# MCU.net
KiCad netlist of a schematic drawn in Altium Designer
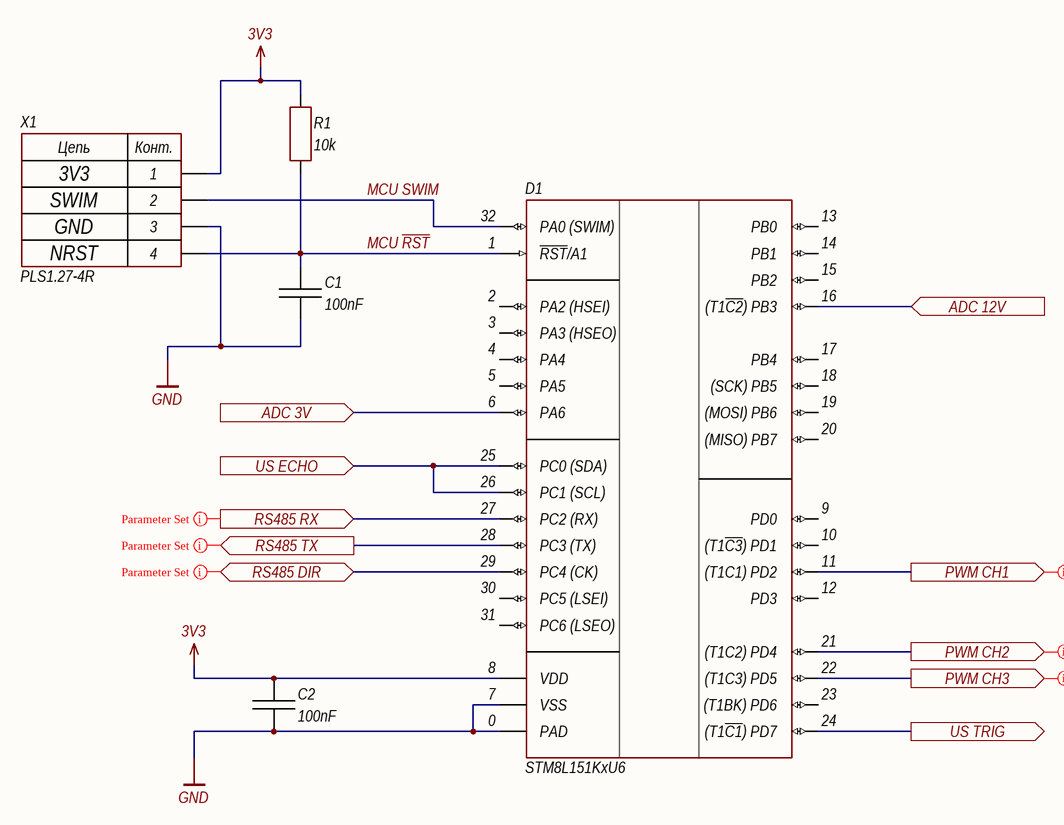
[diagram p0: MCU.SchDoc]

(export (version "E")
  (design (tool "Eeschema 10.0.6"))
  (components
    (comp (ref "C1")
      (value "100nF")
      (footprint "CH0402C")
      (fields (field (name "MANUFACTURER") "CCTC"))
      (libsource (lib "Discrete") (part "Capacitor"))
    )
    (comp (ref "C2")
      (value "100nF")
      (footprint "CH0402C")
      (fields (field (name "MANUFACTURER") "CCTC"))
      (libsource (lib "Discrete") (part "Capacitor"))
    )
    (comp (ref "D1")
      (value "STM8L151KxU6")
      (footprint "32-UFQFPN")
      (description "STM8")
      (fields (field (name "MANUFACTURER") "ST Microelectronics"))
      (libsource (lib "Digital") (part "STM8L151KxU6"))
    )
    (comp (ref "R1")
      (value "10k")
      (footprint "CH0402R")
      (fields (field (name "MANUFACTURER") "Uniroyal Elec"))
      (libsource (lib "Discrete") (part "Resistor"))
    )
    (comp (ref "X1")
      (value "PLS1.27-4R")
      (footprint "CON: PLS1.27-4R")
      (libsource (lib "Connectors") (part "4-Connector"))
    )
  )
  (nets
    (net (code "1") (name "/ADC 3V") (class "Default")
      (node (ref "D1") (pin "6") (pinfunction "PA6_6") (pintype "bidirectional"))
    )
    (net (code "2") (name "/ADC 12V") (class "Default")
      (node (ref "D1") (pin "16") (pinfunction "(T1~{C2})_PB3_16") (pintype "bidirectional"))
    )
    (net (code "3") (name "/MCU SWIM") (class "Default")
      (node (ref "D1") (pin "32") (pinfunction "PA0_(SWIM)_32") (pintype "bidirectional"))
      (node (ref "X1") (pin "2") (pinfunction "2_2") (pintype "passive"))
    )
    (net (code "4") (name "/MCU ~{RST}") (class "Default")
      (node (ref "C1") (pin "2") (pinfunction "2_2") (pintype "power_in"))
      (node (ref "D1") (pin "1") (pinfunction "~{RST}/A1_1") (pintype "input"))
      (node (ref "R1") (pin "1") (pinfunction "1_1") (pintype "passive"))
      (node (ref "X1") (pin "4") (pinfunction "4_4") (pintype "passive"))
    )
    (net (code "5") (name "/PWM CH1") (class "Default")
      (node (ref "D1") (pin "11") (pinfunction "(T1C1)_PD2_11") (pintype "bidirectional"))
    )
    (net (code "6") (name "/PWM CH2") (class "Default")
      (node (ref "D1") (pin "21") (pinfunction "(T1C2)_PD4_21") (pintype "bidirectional"))
    )
    (net (code "7") (name "/PWM CH3") (class "Default")
      (node (ref "D1") (pin "22") (pinfunction "(T1C3)_PD5_22") (pintype "bidirectional"))
    )
    (net (code "8") (name "/RS485 DIR") (class "Default")
      (node (ref "D1") (pin "29") (pinfunction "PC4_(CK)_29") (pintype "bidirectional"))
    )
    (net (code "9") (name "/RS485 RX") (class "Default")
      (node (ref "D1") (pin "27") (pinfunction "PC2_(RX)_27") (pintype "bidirectional"))
    )
    (net (code "10") (name "/RS485 TX") (class "Default")
      (node (ref "D1") (pin "28") (pinfunction "PC3_(TX)_28") (pintype "bidirectional"))
    )
    (net (code "11") (name "/US ECHO") (class "Default")
      (node (ref "D1") (pin "25") (pinfunction "PC0_(SDA)_25") (pintype "bidirectional"))
      (node (ref "D1") (pin "26") (pinfunction "PC1_(SCL)_26") (pintype "bidirectional"))
    )
    (net (code "12") (name "/US TRIG") (class "Default")
      (node (ref "D1") (pin "24") (pinfunction "(T1~{C1})_PD7_24") (pintype "bidirectional"))
    )
    (net (code "13") (name "3V3") (class "Default")
      (node (ref "C2") (pin "2") (pinfunction "2_2") (pintype "power_in"))
      (node (ref "D1") (pin "8") (pinfunction "VDD_8") (pintype "power_in"))
      (node (ref "R1") (pin "2") (pinfunction "2_2") (pintype "passive"))
      (node (ref "X1") (pin "1") (pinfunction "1_1") (pintype "passive"))
    )
    (net (code "14") (name "GND") (class "Default")
      (node (ref "C1") (pin "1") (pinfunction "1_1") (pintype "power_in"))
      (node (ref "C2") (pin "1") (pinfunction "1_1") (pintype "power_in"))
      (node (ref "D1") (pin "0") (pinfunction "PAD_0") (pintype "power_in"))
      (node (ref "D1") (pin "7") (pinfunction "VSS_7") (pintype "power_in"))
      (node (ref "X1") (pin "3") (pinfunction "3_3") (pintype "passive"))
    )
    (net (code "15") (name "unconnected-(D1-(MISO)_PB7-Pad20)") (class "Default")
      (node (ref "D1") (pin "20") (pinfunction "(MISO)_PB7_20") (pintype "bidirectional"))
    )
    (net (code "16") (name "unconnected-(D1-(MOSI)_PB6-Pad19)") (class "Default")
      (node (ref "D1") (pin "19") (pinfunction "(MOSI)_PB6_19") (pintype "bidirectional"))
    )
    (net (code "17") (name "unconnected-(D1-(SCK)_PB5-Pad18)") (class "Default")
      (node (ref "D1") (pin "18") (pinfunction "(SCK)_PB5_18") (pintype "bidirectional"))
    )
    (net (code "18") (name "unconnected-(D1-(T1BK)_PD6-Pad23)") (class "Default")
      (node (ref "D1") (pin "23") (pinfunction "(T1BK)_PD6_23") (pintype "bidirectional"))
    )
    (net (code "19") (name "unconnected-(D1-(T1~{C3})_PD1-Pad10)") (class "Default")
      (node (ref "D1") (pin "10") (pinfunction "(T1~{C3})_PD1_10") (pintype "bidirectional"))
    )
    (net (code "20") (name "unconnected-(D1-PA2_(HSEI)-Pad2)") (class "Default")
      (node (ref "D1") (pin "2") (pinfunction "PA2_(HSEI)_2") (pintype "bidirectional"))
    )
    (net (code "21") (name "unconnected-(D1-PA3_(HSEO)-Pad3)") (class "Default")
      (node (ref "D1") (pin "3") (pinfunction "PA3_(HSEO)_3") (pintype "bidirectional"))
    )
    (net (code "22") (name "unconnected-(D1-PA4-Pad4)") (class "Default")
      (node (ref "D1") (pin "4") (pinfunction "PA4_4") (pintype "bidirectional"))
    )
    (net (code "23") (name "unconnected-(D1-PA5-Pad5)") (class "Default")
      (node (ref "D1") (pin "5") (pinfunction "PA5_5") (pintype "bidirectional"))
    )
    (net (code "24") (name "unconnected-(D1-PB0-Pad13)") (class "Default")
      (node (ref "D1") (pin "13") (pinfunction "PB0_13") (pintype "bidirectional"))
    )
    (net (code "25") (name "unconnected-(D1-PB1-Pad14)") (class "Default")
      (node (ref "D1") (pin "14") (pinfunction "PB1_14") (pintype "bidirectional"))
    )
    (net (code "26") (name "unconnected-(D1-PB2-Pad15)") (class "Default")
      (node (ref "D1") (pin "15") (pinfunction "PB2_15") (pintype "bidirectional"))
    )
    (net (code "27") (name "unconnected-(D1-PB4-Pad17)") (class "Default")
      (node (ref "D1") (pin "17") (pinfunction "PB4_17") (pintype "bidirectional"))
    )
    (net (code "28") (name "unconnected-(D1-PC5_(LSEI)-Pad30)") (class "Default")
      (node (ref "D1") (pin "30") (pinfunction "PC5_(LSEI)_30") (pintype "bidirectional"))
    )
    (net (code "29") (name "unconnected-(D1-PC6_(LSEO)-Pad31)") (class "Default")
      (node (ref "D1") (pin "31") (pinfunction "PC6_(LSEO)_31") (pintype "bidirectional"))
    )
    (net (code "30") (name "unconnected-(D1-PD0-Pad9)") (class "Default")
      (node (ref "D1") (pin "9") (pinfunction "PD0_9") (pintype "bidirectional"))
    )
    (net (code "31") (name "unconnected-(D1-PD3-Pad12)") (class "Default")
      (node (ref "D1") (pin "12") (pinfunction "PD3_12") (pintype "bidirectional"))
    )
  )
)
